# Omnimo_nRF52840.net
KiCad netlist of a schematic drawn in EasyEDA Pro
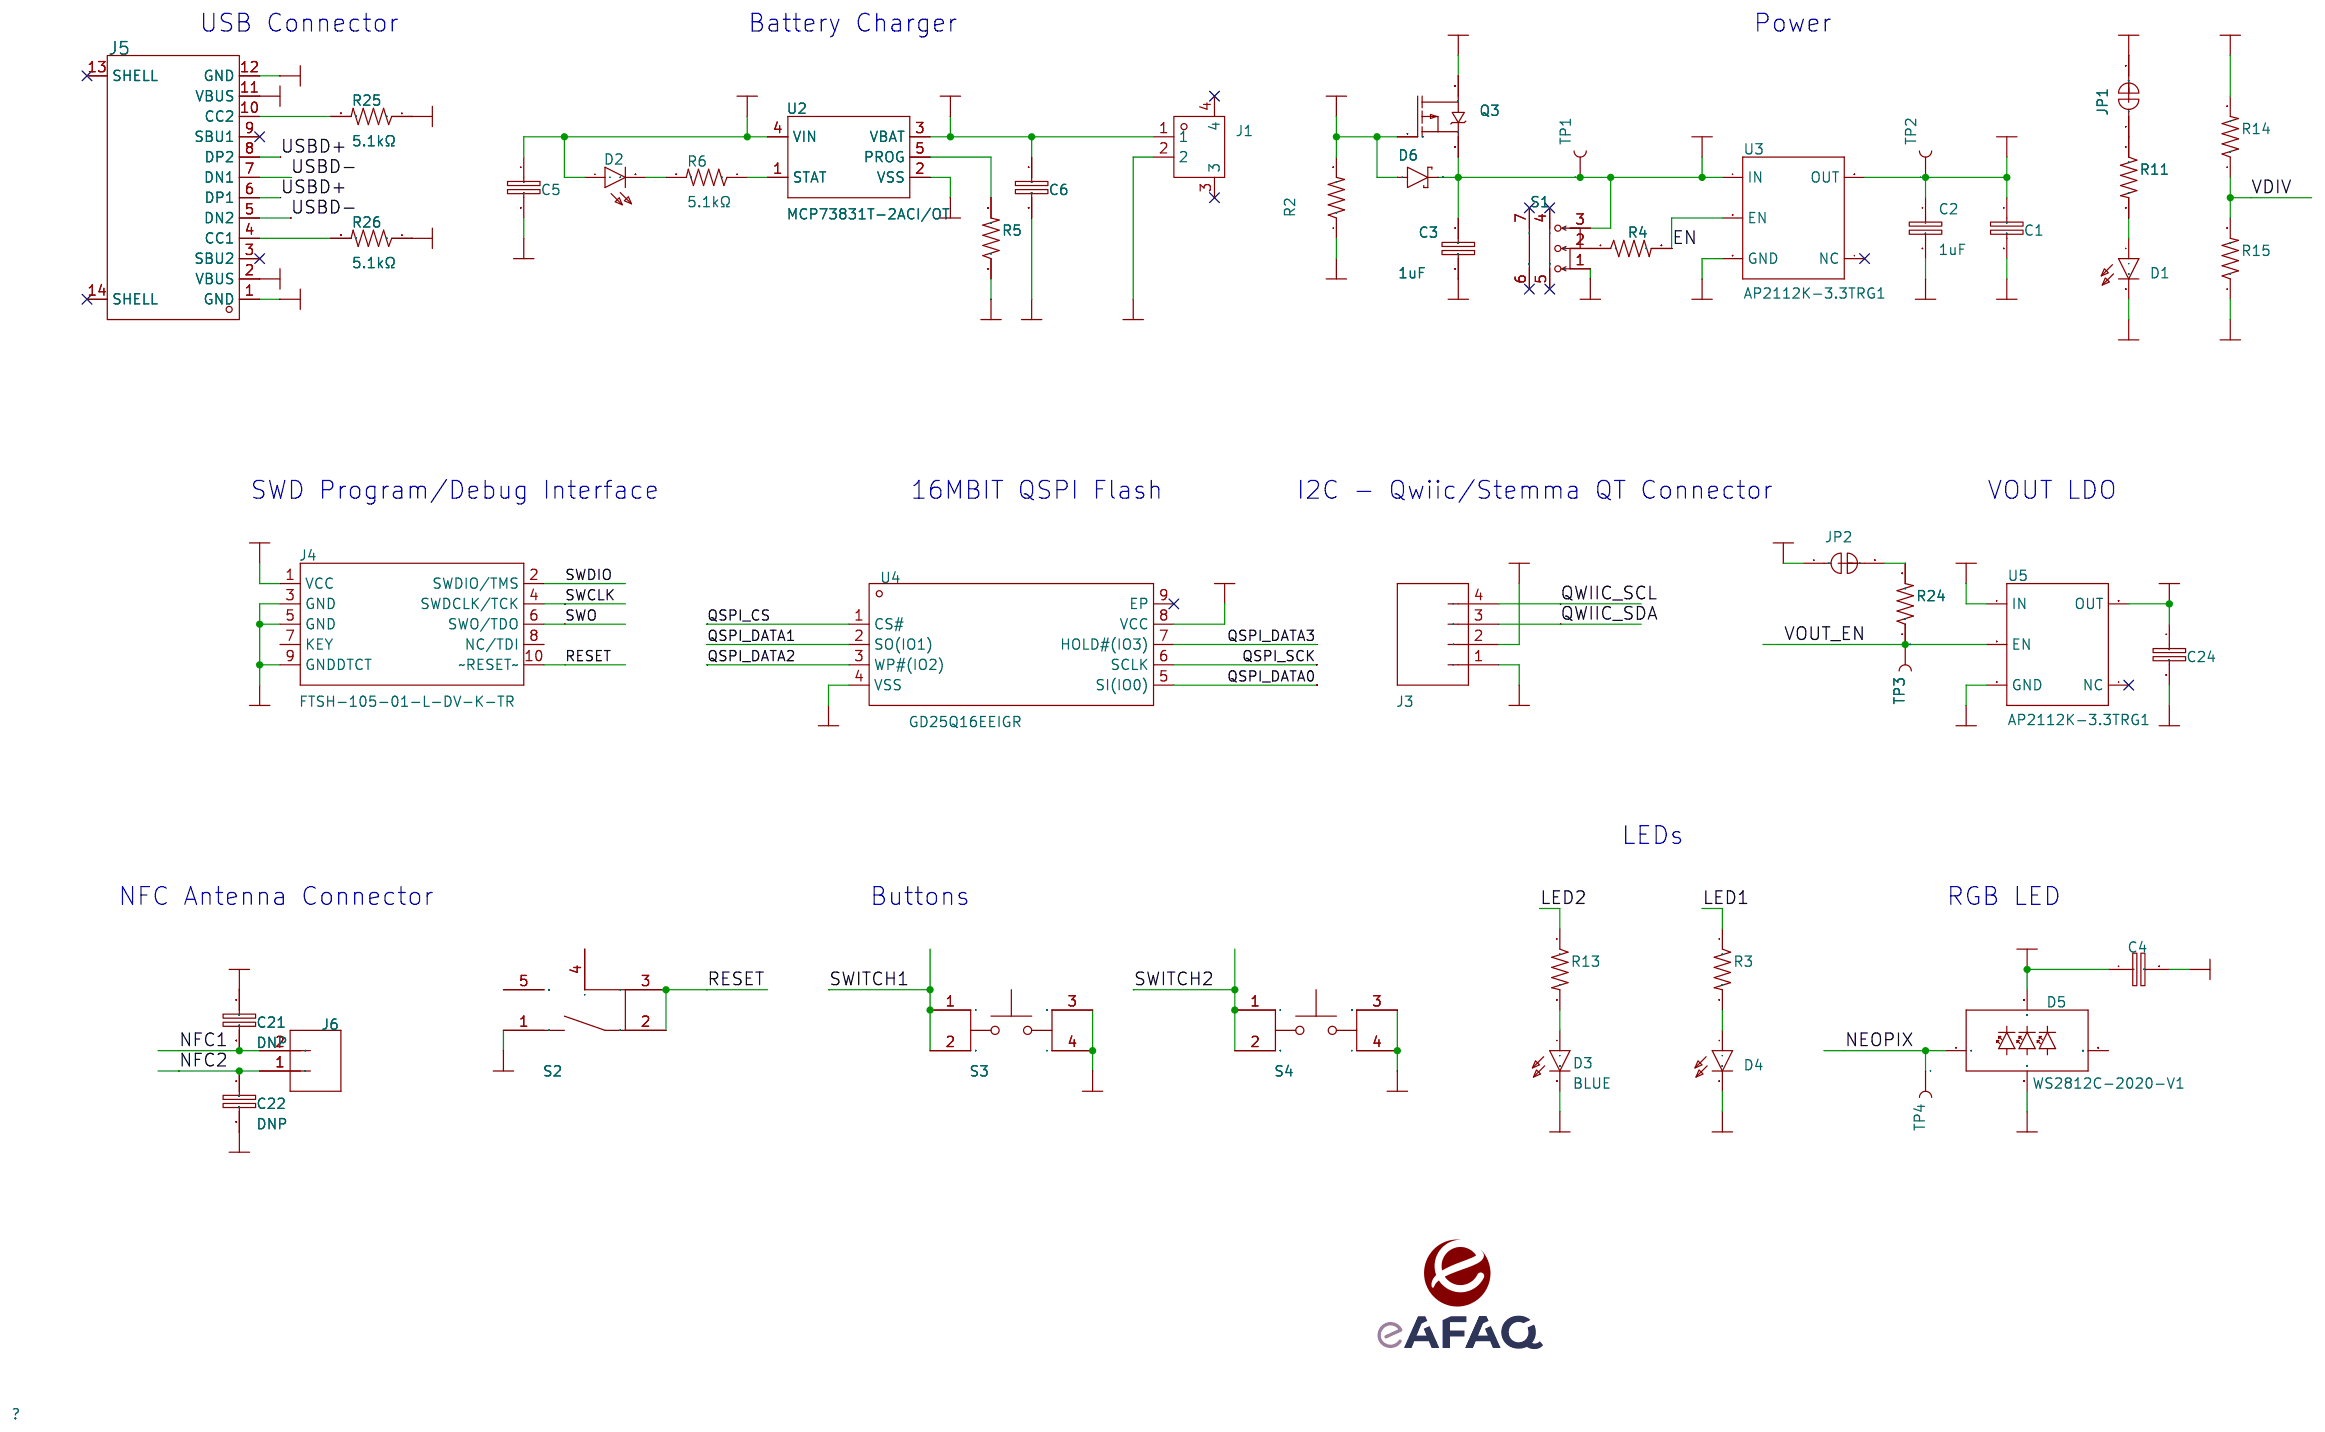
[diagram p0: Omnimo_nrf52840_v1_1_sheet_1]
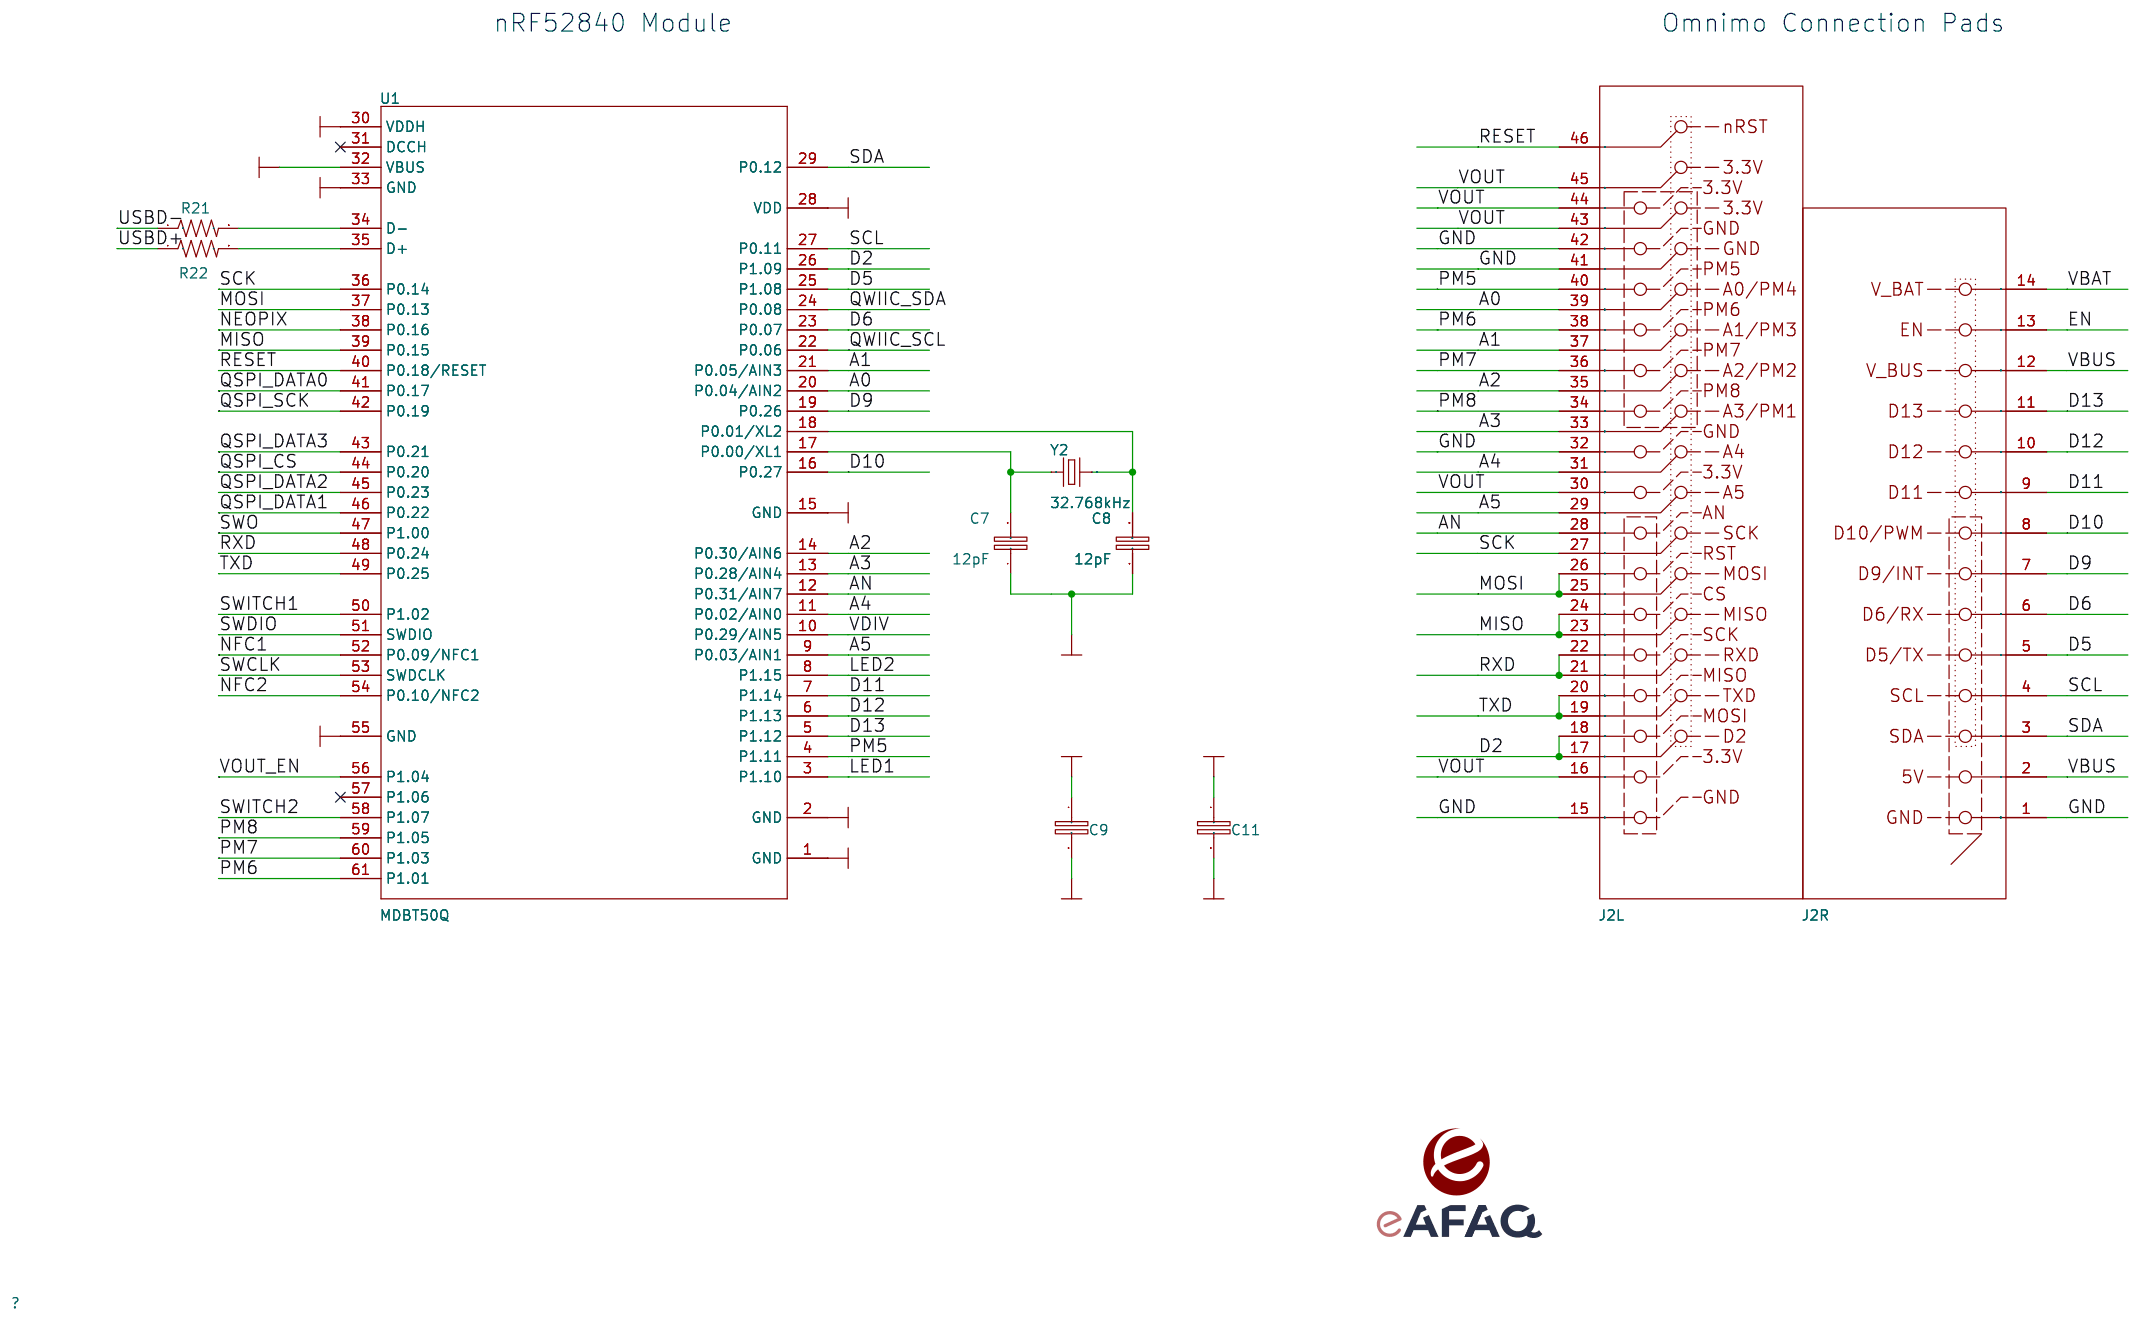
[diagram p1: Omnimo_nrf52840_v1_1_sheet_2]

(export (version "E")
  (design (tool "Eeschema 10.0.6"))
  (components
    (comp (ref "C1")
      (value "10uF")
      (footprint "easyedapro:0603_Nom")
      (fields (field (name "Manufacturer Part") "CC0603KRX5R5BB106"))
      (libsource (lib "easyedapro") (part "10UF-0603-6.3V-20%"))
    )
    (comp (ref "C2")
      (value "1uF")
      (fields
        (field (name "Manufacturer Part") "CL05A105KO5NNNC")
        (field (name "Manufacturer Part Number") "C0402C105K4PAC7867")
      )
      (libsource (lib "easyedapro") (part "1.0UF-0402T-16V-10%"))
    )
    (comp (ref "C3")
      (value "1uF")
      (fields
        (field (name "Manufacturer Part") "CL05A105KO5NNNC")
        (field (name "Manufacturer Part Number") "C0402C105K4PAC7867")
      )
      (libsource (lib "easyedapro") (part "1.0UF-0402T-16V-10%"))
    )
    (comp (ref "C4")
      (value "100nF")
      (fields
        (field (name "Manufacturer Part") "CC0402KRX5R6BB104")
        (field (name "Manufacturer Part Number") "C0402C104K8PACTU")
      )
      (libsource (lib "easyedapro") (part "0.1UF-0603-25V-(+80/-20%)"))
    )
    (comp (ref "C5")
      (value "4.7uF")
      (fields (field (name "Manufacturer Part") "CC0402MRX5R5BB475"))
      (libsource (lib "easyedapro") (part "4.7UF-0603-6.3V-(10%)"))
    )
    (comp (ref "C6")
      (value "4.7uF")
      (fields (field (name "Manufacturer Part") "CC0402MRX5R5BB475"))
      (libsource (lib "easyedapro") (part "4.7UF-0603-6.3V-(10%)"))
    )
    (comp (ref "C21")
      (value "DNP")
      (footprint "easyedapro:0603_Nom")
      (libsource (lib "easyedapro") (part "10UF-0603-6.3V-20%"))
    )
    (comp (ref "C22")
      (value "DNP")
      (footprint "easyedapro:0603_Nom")
      (libsource (lib "easyedapro") (part "10UF-0603-6.3V-20%"))
    )
    (comp (ref "C24")
      (value "10uF")
      (footprint "easyedapro:0603_Nom")
      (fields (field (name "Manufacturer Part") "CC0603KRX5R5BB106"))
      (libsource (lib "easyedapro") (part "10UF-0603-6.3V-20%"))
    )
    (comp (ref "D1")
      (value "RED")
      (fields
        (field (name "Manufacturer Part") "XL-1608SURC-06")
        (field (name "Manufacturer Part Number") "NCD1608W1")
      )
      (libsource (lib "easyedapro") (part "LED-YELLOW0603"))
    )
    (comp (ref "D2")
      (value "ORANGE")
      (fields
        (field (name "Manufacturer Part") "XL-1608UOC-06")
        (field (name "Manufacturer Part Number") "5988050107F")
      )
      (libsource (lib "easyedapro") (part "LED-YELLOW0603"))
    )
    (comp (ref "D3")
      (value "BLUE")
      (footprint "easyedapro:LED-0603_2")
      (fields
        (field (name "Manufacturer") "Dialight")
        (field (name "Manufacturer Part") "XL-1608UBC-04")
        (field (name "Manufacturer Part Number") "5988091107F")
      )
      (libsource (lib "easyedapro") (part "LED-BLUE0603"))
    )
    (comp (ref "D4")
      (value "RED")
      (fields
        (field (name "Manufacturer Part") "XL-1608SURC-06")
        (field (name "Manufacturer Part Number") "NCD1608W1")
      )
      (libsource (lib "easyedapro") (part "LED-YELLOW0603"))
    )
    (comp (ref "D5")
      (value "WS2812C-2020-V1")
      (description "Addressable Lighting Neopixel LED Discrete Red, Green, Blue (RGB) 2.00mm L x 2.00mm W")
      (fields (field (name "Manufacturer Part Number") "WS2812-2020"))
      (libsource (lib "easyedapro") (part "WS2812_2020"))
    )
    (comp (ref "D6")
      (value "BAT60B")
      (fields (field (name "Manufacturer Part Number") "BAT60AE6327HTSA1"))
      (libsource (lib "easyedapro") (part "DIODE-SCHOTTKY-BAT60A"))
    )
    (comp (ref "J1")
      (value "S2B-PH-SM4-TB(LF)(SN)")
      (footprint "easyedapro:CONN-SMD_P2.00_S2B-PH-SM4-TB-LF-SN")
      (fields
        (field (name "Manufacturer") "JST")
        (field (name "Manufacturer Part Number") "S2B-PH-SM4-K-TB (LF)(SN)")
      )
      (libsource (lib "easyedapro") (part "S2B-PH-SM4-TB(LF)(SN)"))
    )
    (comp (ref "J3")
      (value "SM04B-SRSS-TB(LF)(SN)")
      (libsource (lib "easyedapro") (part "JST-4-CONNECTOR-1MM"))
    )
    (comp (ref "J4") (value "FTSH-105-01-L-DV-K-TR") (libsource (lib "easyedapro") (part "CORTEX_DEBUG_PTH")))
    (comp (ref "J5")
      (value "TYPE-C 16PIN 2MD(073)")
      (footprint "easyedapro:USB-C-SMD_TYPE-C-6PIN-2MD-073")
      (fields (field (name "Manufacturer") "SHOU HAN(首韩)"))
      (libsource (lib "easyedapro") (part "TYPE-C 16PIN 2MD(073)"))
    )
    (comp (ref "J6")
      (value "CONN_021X02")
      (footprint "easyedapro:1X02_NFC")
      (libsource (lib "easyedapro") (part "CONN_021X02_NO_SILK"))
    )
    (comp (ref "JP1")
      (value "JUMPER-SMT_2_NC_TRACE_SILK")
      (footprint "easyedapro:SMT-JUMPER_2_NC_TRACE_SILK_2")
      (libsource (lib "easyedapro") (part "JUMPER-SMT_2_NC_TRACE_SILK"))
    )
    (comp (ref "JP2")
      (value "JUMPER-SMT_2_NC_TRACE_SILK")
      (footprint "easyedapro:SMT-JUMPER_2_NC_TRACE_SILK_2")
      (libsource (lib "easyedapro") (part "JUMPER-SMT_2_NC_TRACE_SILK"))
    )
    (comp (ref "Q3") (value "DMG2305UXQ-7") (libsource (lib "easyedapro") (part "MOSFET_PCH-DMG2305UX-7")))
    (comp (ref "R2")
      (value "100kΩ")
      (fields (field (name "Manufacturer Part") "RC0402FR-07100KL"))
      (libsource (lib "easyedapro") (part "10KOHM-0603-1/10W-1%"))
    )
    (comp (ref "R3")
      (value "2.2kΩ")
      (fields
        (field (name "Manufacturer Part") "RC0402FR-072K2L")
        (field (name "Manufacturer Part Number") "RC0402FR-071KL")
      )
      (libsource (lib "easyedapro") (part "1KOHM-0603-1/10W-1%"))
    )
    (comp (ref "R4")
      (value "100kΩ")
      (fields
        (field (name "Manufacturer Part") "RC0402FR-07100KL")
        (field (name "Manufacturer Part Number") "RC0402FR-0710KL")
      )
      (libsource (lib "easyedapro") (part "1KOHM-0603-1/10W-1%"))
    )
    (comp (ref "R5")
      (value "2kΩ")
      (fields (field (name "Manufacturer Part") "RC0402JR-072KL"))
      (libsource (lib "easyedapro") (part "2.0KOHM-0603-1/10W-5%"))
    )
    (comp (ref "R6")
      (value "5.1kΩ")
      (fields (field (name "Manufacturer Part") "RC0402FR-075K1L"))
      (libsource (lib "easyedapro") (part "5.1KOHM-0402T-1/16W-1%"))
    )
    (comp (ref "R11")
      (value "10kΩ")
      (fields
        (field (name "Manufacturer Part") "RC0402FR-0710KL")
        (field (name "Manufacturer Part Number") "RC0402FR-071KL")
      )
      (libsource (lib "easyedapro") (part "1KOHM-0603-1/10W-1%"))
    )
    (comp (ref "R13")
      (value "2.2kΩ")
      (fields
        (field (name "Manufacturer Part") "RC0402FR-072K2L")
        (field (name "Manufacturer Part Number") "RC0402FR-071KL")
      )
      (libsource (lib "easyedapro") (part "1KOHM-0603-1/10W-1%"))
    )
    (comp (ref "R14")
      (value "100kΩ")
      (fields
        (field (name "Manufacturer Part") "RC0402DR-07100KL")
        (field (name "Manufacturer Part Number") "RC0402FR-07100KL")
      )
      (libsource (lib "easyedapro") (part "10KOHM-0603-1/10W-1%"))
    )
    (comp (ref "R15")
      (value "100kΩ")
      (fields
        (field (name "Manufacturer Part") "RC0402DR-07100KL")
        (field (name "Manufacturer Part Number") "RC0402FR-07100KL")
      )
      (libsource (lib "easyedapro") (part "10KOHM-0603-1/10W-1%"))
    )
    (comp (ref "R24")
      (value "100kΩ")
      (fields (field (name "Manufacturer Part") "RC0402FR-07100KL"))
      (libsource (lib "easyedapro") (part "10KOHM-0603-1/10W-1%"))
    )
    (comp (ref "R25")
      (value "5.1kΩ")
      (fields (field (name "Manufacturer Part") "RC0402FR-075K1L"))
      (libsource (lib "easyedapro") (part "5.1KOHM-0402T-1/16W-1%"))
    )
    (comp (ref "R26")
      (value "5.1kΩ")
      (fields (field (name "Manufacturer Part") "RC0402FR-075K1L"))
      (libsource (lib "easyedapro") (part "5.1KOHM-0402T-1/16W-1%"))
    )
    (comp (ref "S1")
      (value "TA-3514-A1-B")
      (footprint "easyedapro:SW-SMD_TA-3514-A1-B")
      (fields (field (name "Manufacturer") "Yuandi(元迪)"))
      (libsource (lib "easyedapro") (part "TA-3514-A1-B"))
    )
    (comp (ref "S2") (value "R-667270") (libsource (lib "easyedapro") (part "Tact Switch - PTS815 Series_1")))
    (comp (ref "S3")
      (value "PTS815SJG250SMTRLFS")
      (libsource (lib "easyedapro") (part "Tact Switch - PTS815 Series"))
    )
    (comp (ref "S4")
      (value "PTS815SJG250SMTRLFS")
      (libsource (lib "easyedapro") (part "Tact Switch - PTS815 Series"))
    )
    (comp (ref "TP1")
      (value "TEST-POINT3X5")
      (footprint "easyedapro:TEST_POINT_1mm")
      (description "Test Point")
      (libsource (lib "easyedapro") (part "TEST-POINT3X5"))
    )
    (comp (ref "TP2")
      (value "TEST-POINT3X5")
      (footprint "easyedapro:TEST_POINT_1mm")
      (description "Test Point")
      (libsource (lib "easyedapro") (part "TEST-POINT3X5"))
    )
    (comp (ref "TP3")
      (value "TEST-POINT3X5")
      (footprint "easyedapro:TEST_POINT_1mm")
      (description "Test Point")
      (libsource (lib "easyedapro") (part "TEST-POINT3X5"))
    )
    (comp (ref "TP4")
      (value "TEST-POINT3X5")
      (footprint "easyedapro:TEST_POINT_1mm")
      (description "Test Point")
      (libsource (lib "easyedapro") (part "TEST-POINT3X5"))
    )
    (comp (ref "U2") (value "MCP73831T-2ACI/OT") (libsource (lib "easyedapro") (part "MCP73831")))
    (comp (ref "U3") (value "AP2112K-3.3TRG1") (libsource (lib "easyedapro") (part "V_REG_AP2112K-3.3V")))
    (comp (ref "U4")
      (value "GD25Q16EEIGR")
      (footprint "easyedapro:USON-8_L3.0-W2.0-P0.50-BL-EP_GD25QXX")
      (fields
        (field (name "Manufacturer") "GigaDevice(兆易创新)")
        (field (name "Manufacturer Part Number") "GD25WQ16EEIGR")
      )
      (libsource (lib "easyedapro") (part "GD25Q16EEIGR"))
    )
    (comp (ref "U5") (value "AP2112K-3.3TRG1") (libsource (lib "easyedapro") (part "V_REG_AP2112K-3.3V")))
    (comp (ref "C7")
      (value "12pF")
      (footprint "easyedapro:0402_NOM")
      (description "12pF, 0402, 50V, 1%")
      (fields (field (name "Manufacturer") "AVX") (field (name "Manufacturer Part") "04025U120FAT2A"))
      (libsource (lib "easyedapro") (part "15PF-0603-50V-5%"))
    )
    (comp (ref "C8")
      (value "12pF")
      (footprint "easyedapro:0402_NOM")
      (description "12pF, 0402, 50V, 1%")
      (fields (field (name "Manufacturer") "AVX") (field (name "Manufacturer Part") "04025U120FAT2A"))
      (libsource (lib "easyedapro") (part "15PF-0603-50V-5%"))
    )
    (comp (ref "C9")
      (value "10uF")
      (footprint "easyedapro:0603_Nom")
      (fields (field (name "Manufacturer Part") "CC0603KRX5R5BB106"))
      (libsource (lib "easyedapro") (part "10UF-0603-6.3V-20%"))
    )
    (comp (ref "C11")
      (value "100nF")
      (fields
        (field (name "Manufacturer Part") "CC0402KRX5R6BB104")
        (field (name "Manufacturer Part Number") "C0402C104K8PACTU")
      )
      (libsource (lib "easyedapro") (part "0.1UF-0603-25V-(+80/-20%)"))
    )
    (comp (ref "J2L")
      (value "omnimo_Header_left")
      (footprint "easyedapro:Omnimo_HDR_Left_nRF52_2 - without silk screen")
      (libsource (lib "easyedapro") (part "omnimo_HDR_Left"))
    )
    (comp (ref "J2R")
      (value "omnimo_Header_right")
      (footprint "easyedapro:Omnimo_HDR_Right_nRF52_2 - without silk screen")
      (libsource (lib "easyedapro") (part "omnimo_HDR_Right"))
    )
    (comp (ref "R21")
      (value "27Ω")
      (footprint "easyedapro:0402_NOM")
      (description "RES 27 OHM 1% 1/10W 0402 SMD")
      (fields
        (field (name "Manufacturer") "Panasonic Electronic Components")
        (field (name "Manufacturer Part") "ERJ-U02F27R0X")
      )
      (libsource (lib "easyedapro") (part "27OHM-0603-1/10W-1%"))
    )
    (comp (ref "R22")
      (value "27Ω")
      (footprint "easyedapro:0402_NOM")
      (description "RES 27 OHM 1% 1/10W 0402 SMD")
      (fields
        (field (name "Manufacturer") "Panasonic Electronic Components")
        (field (name "Manufacturer Part") "ERJ-U02F27R0X")
      )
      (libsource (lib "easyedapro") (part "27OHM-0603-1/10W-1%"))
    )
    (comp (ref "U1")
      (value "MDBT50Q")
      (footprint "easyedapro:MDBT50Q-1MV2")
      (description "MDBT50 Bluetooth Low Energy Module based on Noridc nRF52840")
      (fields (field (name "Manufacturer") "Raytac") (field (name "Manufacturer Part") "MDBT50Q-1MV2"))
      (libsource (lib "easyedapro") (part "MDBT50Q"))
    )
    (comp (ref "Y2")
      (value "32.768kHz")
      (fields (field (name "Manufacturer Part") "ABS07-32.768KHZ-T"))
      (libsource (lib "easyedapro") (part "CRYSTAL-32.768KHZSMD-3.2X1.5"))
    )
  )
  (nets
    (net (code "1") (name "3.3V") (class "Default")
      (node (ref "C1") (pin "1") (pinfunction "1_1") (pintype "unspecified"))
      (node (ref "C11") (pin "1") (pinfunction "1_1") (pintype "unspecified"))
      (node (ref "C2") (pin "1") (pinfunction "1_1") (pintype "unspecified"))
      (node (ref "C4") (pin "1") (pinfunction "1_1") (pintype "unspecified"))
      (node (ref "C9") (pin "1") (pinfunction "1_1") (pintype "unspecified"))
      (node (ref "D5") (pin "VCC") (pinfunction "VCC_VCC") (pintype "unspecified"))
      (node (ref "J4") (pin "1") (pinfunction "VCC_1") (pintype "unspecified"))
      (node (ref "JP1") (pin "2") (pinfunction "2_2") (pintype "unspecified"))
      (node (ref "JP2") (pin "1") (pinfunction "1_1") (pintype "unspecified"))
      (node (ref "TP2") (pin "P$1") (pinfunction "1_P$1") (pintype "unspecified"))
      (node (ref "U1") (pin "28") (pinfunction "VDD_28") (pintype "unspecified"))
      (node (ref "U1") (pin "30") (pinfunction "VDDH_30") (pintype "unspecified"))
      (node (ref "U3") (pin "5") (pinfunction "OUT_5") (pintype "unspecified"))
      (node (ref "U4") (pin "8") (pinfunction "VCC_8") (pintype "unspecified"))
    )
    (net (code "2") (name "A0") (class "Default")
      (node (ref "J2L") (pin "39") (pinfunction "39_39") (pintype "unspecified"))
      (node (ref "U1") (pin "20") (pinfunction "P0.04/AIN2_20") (pintype "unspecified"))
    )
    (net (code "3") (name "A1") (class "Default")
      (node (ref "J2L") (pin "37") (pinfunction "37_37") (pintype "unspecified"))
      (node (ref "U1") (pin "21") (pinfunction "P0.05/AIN3_21") (pintype "unspecified"))
    )
    (net (code "4") (name "A2") (class "Default")
      (node (ref "J2L") (pin "35") (pinfunction "35_35") (pintype "unspecified"))
      (node (ref "U1") (pin "14") (pinfunction "P0.30/AIN6_14") (pintype "unspecified"))
    )
    (net (code "5") (name "A3") (class "Default")
      (node (ref "J2L") (pin "33") (pinfunction "33_33") (pintype "unspecified"))
      (node (ref "U1") (pin "13") (pinfunction "P0.28/AIN4_13") (pintype "unspecified"))
    )
    (net (code "6") (name "A4") (class "Default")
      (node (ref "J2L") (pin "31") (pinfunction "31_31") (pintype "unspecified"))
      (node (ref "U1") (pin "11") (pinfunction "P0.02/AIN0_11") (pintype "unspecified"))
    )
    (net (code "7") (name "A5") (class "Default")
      (node (ref "J2L") (pin "29") (pinfunction "29_29") (pintype "unspecified"))
      (node (ref "U1") (pin "9") (pinfunction "P0.03/AIN1_9") (pintype "unspecified"))
    )
    (net (code "8") (name "AN") (class "Default")
      (node (ref "J2L") (pin "28") (pinfunction "28_28") (pintype "unspecified"))
      (node (ref "U1") (pin "12") (pinfunction "P0.31/AIN7_12") (pintype "unspecified"))
    )
    (net (code "9") (name "D2") (class "Default")
      (node (ref "J2L") (pin "17") (pinfunction "17_17") (pintype "unspecified"))
      (node (ref "J2L") (pin "18") (pinfunction "18_18") (pintype "unspecified"))
      (node (ref "U1") (pin "26") (pinfunction "P1.09_26") (pintype "unspecified"))
    )
    (net (code "10") (name "D5") (class "Default")
      (node (ref "J2R") (pin "5") (pinfunction "5_5") (pintype "unspecified"))
      (node (ref "U1") (pin "25") (pinfunction "P1.08_25") (pintype "unspecified"))
    )
    (net (code "11") (name "D6") (class "Default")
      (node (ref "J2R") (pin "6") (pinfunction "6_6") (pintype "unspecified"))
      (node (ref "U1") (pin "23") (pinfunction "P0.07_23") (pintype "unspecified"))
    )
    (net (code "12") (name "D9") (class "Default")
      (node (ref "J2R") (pin "7") (pinfunction "7_7") (pintype "unspecified"))
      (node (ref "U1") (pin "19") (pinfunction "P0.26_19") (pintype "unspecified"))
    )
    (net (code "13") (name "D10") (class "Default")
      (node (ref "J2R") (pin "8") (pinfunction "8_8") (pintype "unspecified"))
      (node (ref "U1") (pin "16") (pinfunction "P0.27_16") (pintype "unspecified"))
    )
    (net (code "14") (name "D11") (class "Default")
      (node (ref "J2R") (pin "9") (pinfunction "9_9") (pintype "unspecified"))
      (node (ref "U1") (pin "7") (pinfunction "P1.14_7") (pintype "unspecified"))
    )
    (net (code "15") (name "D12") (class "Default")
      (node (ref "J2R") (pin "10") (pinfunction "10_10") (pintype "unspecified"))
      (node (ref "U1") (pin "6") (pinfunction "P1.13_6") (pintype "unspecified"))
    )
    (net (code "16") (name "D13") (class "Default")
      (node (ref "J2R") (pin "11") (pinfunction "11_11") (pintype "unspecified"))
      (node (ref "U1") (pin "5") (pinfunction "P1.12_5") (pintype "unspecified"))
    )
    (net (code "17") (name "EN") (class "Default")
      (node (ref "J2R") (pin "13") (pinfunction "13_13") (pintype "unspecified"))
      (node (ref "R4") (pin "2") (pinfunction "2_2") (pintype "unspecified"))
      (node (ref "U3") (pin "3") (pinfunction "EN_3") (pintype "unspecified"))
    )
    (net (code "18") (name "GND") (class "Default")
      (node (ref "C1") (pin "2") (pinfunction "2_2") (pintype "unspecified"))
      (node (ref "C11") (pin "2") (pinfunction "2_2") (pintype "unspecified"))
      (node (ref "C2") (pin "2") (pinfunction "2_2") (pintype "unspecified"))
      (node (ref "C21") (pin "1") (pinfunction "1_1") (pintype "unspecified"))
      (node (ref "C22") (pin "2") (pinfunction "2_2") (pintype "unspecified"))
      (node (ref "C24") (pin "2") (pinfunction "2_2") (pintype "unspecified"))
      (node (ref "C3") (pin "2") (pinfunction "2_2") (pintype "unspecified"))
      (node (ref "C4") (pin "2") (pinfunction "2_2") (pintype "unspecified"))
      (node (ref "C5") (pin "2") (pinfunction "2_2") (pintype "unspecified"))
      (node (ref "C6") (pin "2") (pinfunction "2_2") (pintype "unspecified"))
      (node (ref "C7") (pin "1") (pinfunction "1_1") (pintype "unspecified"))
      (node (ref "C8") (pin "1") (pinfunction "1_1") (pintype "unspecified"))
      (node (ref "C9") (pin "2") (pinfunction "2_2") (pintype "unspecified"))
      (node (ref "D1") (pin "C") (pinfunction "C_C") (pintype "unspecified"))
      (node (ref "D3") (pin "C") (pinfunction "C_C") (pintype "unspecified"))
      (node (ref "D4") (pin "C") (pinfunction "C_C") (pintype "unspecified"))
      (node (ref "D5") (pin "GND") (pinfunction "GND_GND") (pintype "unspecified"))
      (node (ref "J1") (pin "2") (pinfunction "2_2") (pintype "unspecified"))
      (node (ref "J2L") (pin "15") (pinfunction "15_15") (pintype "unspecified"))
      (node (ref "J2L") (pin "32") (pinfunction "32_32") (pintype "unspecified"))
      (node (ref "J2L") (pin "41") (pinfunction "41_41") (pintype "unspecified"))
      (node (ref "J2L") (pin "42") (pinfunction "42_42") (pintype "unspecified"))
      (node (ref "J2R") (pin "1") (pinfunction "GND_1") (pintype "unspecified"))
      (node (ref "J3") (pin "1") (pinfunction "1_1") (pintype "unspecified"))
      (node (ref "J4") (pin "3") (pinfunction "GND_3") (pintype "unspecified"))
      (node (ref "J4") (pin "5") (pinfunction "GND_5") (pintype "unspecified"))
      (node (ref "J4") (pin "9") (pinfunction "GNDDTCT_9") (pintype "unspecified"))
      (node (ref "J5") (pin "1") (pinfunction "GND_1") (pintype "input"))
      (node (ref "J5") (pin "12") (pinfunction "GND_12") (pintype "input"))
      (node (ref "R15") (pin "1") (pinfunction "1_1") (pintype "unspecified"))
      (node (ref "R2") (pin "1") (pinfunction "1_1") (pintype "unspecified"))
      (node (ref "R25") (pin "1") (pinfunction "1_1") (pintype "unspecified"))
      (node (ref "R26") (pin "1") (pinfunction "1_1") (pintype "unspecified"))
      (node (ref "R5") (pin "1") (pinfunction "1_1") (pintype "unspecified"))
      (node (ref "S1") (pin "1") (pinfunction "1_1") (pintype "unspecified"))
      (node (ref "S2") (pin "1") (pinfunction "1_1") (pintype "unspecified"))
      (node (ref "S3") (pin "3") (pinfunction "3_3") (pintype "unspecified"))
      (node (ref "S3") (pin "4") (pinfunction "4_4") (pintype "unspecified"))
      (node (ref "S4") (pin "3") (pinfunction "3_3") (pintype "unspecified"))
      (node (ref "S4") (pin "4") (pinfunction "4_4") (pintype "unspecified"))
      (node (ref "U1") (pin "1") (pinfunction "GND_1") (pintype "unspecified"))
      (node (ref "U1") (pin "15") (pinfunction "GND_15") (pintype "unspecified"))
      (node (ref "U1") (pin "2") (pinfunction "GND_2") (pintype "unspecified"))
      (node (ref "U1") (pin "33") (pinfunction "GND_33") (pintype "unspecified"))
      (node (ref "U1") (pin "55") (pinfunction "GND_55") (pintype "unspecified"))
      (node (ref "U2") (pin "2") (pinfunction "VSS_2") (pintype "unspecified"))
      (node (ref "U3") (pin "2") (pinfunction "GND_2") (pintype "unspecified"))
      (node (ref "U4") (pin "4") (pinfunction "VSS_4") (pintype "unspecified"))
      (node (ref "U5") (pin "2") (pinfunction "GND_2") (pintype "unspecified"))
    )
    (net (code "19") (name "LED1") (class "Default")
      (node (ref "R3") (pin "1") (pinfunction "1_1") (pintype "unspecified"))
      (node (ref "U1") (pin "3") (pinfunction "P1.10_3") (pintype "unspecified"))
    )
    (net (code "20") (name "LED2") (class "Default")
      (node (ref "R13") (pin "1") (pinfunction "1_1") (pintype "unspecified"))
      (node (ref "U1") (pin "8") (pinfunction "P1.15_8") (pintype "unspecified"))
    )
    (net (code "21") (name "MISO") (class "Default")
      (node (ref "J2L") (pin "23") (pinfunction "23_23") (pintype "unspecified"))
      (node (ref "J2L") (pin "24") (pinfunction "24_24") (pintype "unspecified"))
      (node (ref "U1") (pin "39") (pinfunction "P0.15_39") (pintype "unspecified"))
    )
    (net (code "22") (name "MOSI") (class "Default")
      (node (ref "J2L") (pin "25") (pinfunction "25_25") (pintype "unspecified"))
      (node (ref "J2L") (pin "26") (pinfunction "26_26") (pintype "unspecified"))
      (node (ref "U1") (pin "37") (pinfunction "P0.13_37") (pintype "unspecified"))
    )
    (net (code "23") (name "NEOPIX") (class "Default")
      (node (ref "D5") (pin "DI") (pinfunction "DI_DI") (pintype "unspecified"))
      (node (ref "TP4") (pin "P$1") (pinfunction "1_P$1") (pintype "unspecified"))
      (node (ref "U1") (pin "38") (pinfunction "P0.16_38") (pintype "unspecified"))
    )
    (net (code "24") (name "NFC1") (class "Default")
      (node (ref "C21") (pin "2") (pinfunction "2_2") (pintype "unspecified"))
      (node (ref "J6") (pin "2") (pinfunction "2_2") (pintype "unspecified"))
      (node (ref "U1") (pin "52") (pinfunction "P0.09/NFC1_52") (pintype "unspecified"))
    )
    (net (code "25") (name "NFC2") (class "Default")
      (node (ref "C22") (pin "1") (pinfunction "1_1") (pintype "unspecified"))
      (node (ref "J6") (pin "1") (pinfunction "1_1") (pintype "unspecified"))
      (node (ref "U1") (pin "54") (pinfunction "P0.10/NFC2_54") (pintype "unspecified"))
    )
    (net (code "26") (name "Net-(D1-PadA)") (class "Default")
      (node (ref "D1") (pin "A") (pinfunction "A_A") (pintype "unspecified"))
      (node (ref "R11") (pin "2") (pinfunction "2_2") (pintype "unspecified"))
    )
    (net (code "27") (name "Net-(D2-PadC)") (class "Default")
      (node (ref "D2") (pin "C") (pinfunction "C_C") (pintype "unspecified"))
      (node (ref "R6") (pin "2") (pinfunction "2_2") (pintype "unspecified"))
    )
    (net (code "28") (name "Net-(D3-PadA)") (class "Default")
      (node (ref "D3") (pin "A") (pinfunction "A_A") (pintype "unspecified"))
      (node (ref "R13") (pin "2") (pinfunction "2_2") (pintype "unspecified"))
    )
    (net (code "29") (name "Net-(D4-PadA)") (class "Default")
      (node (ref "D4") (pin "A") (pinfunction "A_A") (pintype "unspecified"))
      (node (ref "R3") (pin "2") (pinfunction "2_2") (pintype "unspecified"))
    )
    (net (code "30") (name "Net-(J5-CC1)") (class "Default")
      (node (ref "J5") (pin "4") (pinfunction "CC1_4") (pintype "input"))
      (node (ref "R26") (pin "2") (pinfunction "2_2") (pintype "unspecified"))
    )
    (net (code "31") (name "Net-(J5-CC2)") (class "Default")
      (node (ref "J5") (pin "10") (pinfunction "CC2_10") (pintype "input"))
      (node (ref "R25") (pin "2") (pinfunction "2_2") (pintype "unspecified"))
    )
    (net (code "32") (name "Net-(JP1-Pad1)") (class "Default")
      (node (ref "JP1") (pin "1") (pinfunction "1_1") (pintype "unspecified"))
      (node (ref "R11") (pin "1") (pinfunction "1_1") (pintype "unspecified"))
    )
    (net (code "33") (name "Net-(JP2-Pad2)") (class "Default")
      (node (ref "JP2") (pin "2") (pinfunction "2_2") (pintype "unspecified"))
      (node (ref "R24") (pin "2") (pinfunction "2_2") (pintype "unspecified"))
    )
    (net (code "34") (name "Net-(R4-Pad1)") (class "Default")
      (node (ref "R4") (pin "1") (pinfunction "1_1") (pintype "unspecified"))
      (node (ref "S1") (pin "2") (pinfunction "2_2") (pintype "unspecified"))
    )
    (net (code "35") (name "Net-(U1-D+)") (class "Default")
      (node (ref "R22") (pin "2") (pinfunction "2_2") (pintype "unspecified"))
      (node (ref "U1") (pin "35") (pinfunction "D+_35") (pintype "unspecified"))
    )
    (net (code "36") (name "Net-(U1-D-)") (class "Default")
      (node (ref "R21") (pin "2") (pinfunction "2_2") (pintype "unspecified"))
      (node (ref "U1") (pin "34") (pinfunction "D-_34") (pintype "unspecified"))
    )
    (net (code "37") (name "Net-(U1-P0.00{slash}XL1)") (class "Default")
      (node (ref "C7") (pin "2") (pinfunction "2_2") (pintype "unspecified"))
      (node (ref "U1") (pin "17") (pinfunction "P0.00/XL1_17") (pintype "unspecified"))
      (node (ref "Y2") (pin "P$1") (pinfunction "1_P$1") (pintype "unspecified"))
    )
    (net (code "38") (name "Net-(U1-P0.01{slash}XL2)") (class "Default")
      (node (ref "C8") (pin "2") (pinfunction "2_2") (pintype "unspecified"))
      (node (ref "U1") (pin "18") (pinfunction "P0.01/XL2_18") (pintype "unspecified"))
      (node (ref "Y2") (pin "P$2") (pinfunction "2_P$2") (pintype "unspecified"))
    )
    (net (code "39") (name "Net-(U2-PROG)") (class "Default")
      (node (ref "R5") (pin "2") (pinfunction "2_2") (pintype "unspecified"))
      (node (ref "U2") (pin "5") (pinfunction "PROG_5") (pintype "unspecified"))
    )
    (net (code "40") (name "Net-(U2-STAT)") (class "Default")
      (node (ref "R6") (pin "1") (pinfunction "1_1") (pintype "unspecified"))
      (node (ref "U2") (pin "1") (pinfunction "STAT_1") (pintype "output"))
    )
    (net (code "41") (name "PM5") (class "Default")
      (node (ref "J2L") (pin "40") (pinfunction "40_40") (pintype "unspecified"))
      (node (ref "U1") (pin "4") (pinfunction "P1.11_4") (pintype "unspecified"))
    )
    (net (code "42") (name "PM6") (class "Default")
      (node (ref "J2L") (pin "38") (pinfunction "38_38") (pintype "unspecified"))
      (node (ref "U1") (pin "61") (pinfunction "P1.01_61") (pintype "unspecified"))
    )
    (net (code "43") (name "PM7") (class "Default")
      (node (ref "J2L") (pin "36") (pinfunction "36_36") (pintype "unspecified"))
      (node (ref "U1") (pin "60") (pinfunction "P1.03_60") (pintype "unspecified"))
    )
    (net (code "44") (name "PM8") (class "Default")
      (node (ref "J2L") (pin "34") (pinfunction "34_34") (pintype "unspecified"))
      (node (ref "U1") (pin "59") (pinfunction "P1.05_59") (pintype "unspecified"))
    )
    (net (code "45") (name "QSPI_CS") (class "Default")
      (node (ref "U1") (pin "44") (pinfunction "P0.20_44") (pintype "unspecified"))
      (node (ref "U4") (pin "1") (pinfunction "CS#_1") (pintype "unspecified"))
    )
    (net (code "46") (name "QSPI_DATA0") (class "Default")
      (node (ref "U1") (pin "41") (pinfunction "P0.17_41") (pintype "unspecified"))
      (node (ref "U4") (pin "5") (pinfunction "SI(IO0)_5") (pintype "unspecified"))
    )
    (net (code "47") (name "QSPI_DATA1") (class "Default")
      (node (ref "U1") (pin "46") (pinfunction "P0.22_46") (pintype "unspecified"))
      (node (ref "U4") (pin "2") (pinfunction "SO(IO1)_2") (pintype "unspecified"))
    )
    (net (code "48") (name "QSPI_DATA2") (class "Default")
      (node (ref "U1") (pin "45") (pinfunction "P0.23_45") (pintype "unspecified"))
      (node (ref "U4") (pin "3") (pinfunction "WP#(IO2)_3") (pintype "unspecified"))
    )
    (net (code "49") (name "QSPI_DATA3") (class "Default")
      (node (ref "U1") (pin "43") (pinfunction "P0.21_43") (pintype "unspecified"))
      (node (ref "U4") (pin "7") (pinfunction "HOLD#(IO3)_7") (pintype "unspecified"))
    )
    (net (code "50") (name "QSPI_SCK") (class "Default")
      (node (ref "U1") (pin "42") (pinfunction "P0.19_42") (pintype "unspecified"))
      (node (ref "U4") (pin "6") (pinfunction "SCLK_6") (pintype "unspecified"))
    )
    (net (code "51") (name "QWIIC_SCL") (class "Default")
      (node (ref "J3") (pin "4") (pinfunction "4_4") (pintype "unspecified"))
      (node (ref "U1") (pin "22") (pinfunction "P0.06_22") (pintype "unspecified"))
    )
    (net (code "52") (name "QWIIC_SDA") (class "Default")
      (node (ref "J3") (pin "3") (pinfunction "3_3") (pintype "unspecified"))
      (node (ref "U1") (pin "24") (pinfunction "P0.08_24") (pintype "unspecified"))
    )
    (net (code "53") (name "RESET") (class "Default")
      (node (ref "J2L") (pin "46") (pinfunction "46_46") (pintype "unspecified"))
      (node (ref "J4") (pin "10") (pinfunction "~RESET~_10") (pintype "unspecified"))
      (node (ref "S2") (pin "2") (pinfunction "2_2") (pintype "unspecified"))
      (node (ref "S2") (pin "3") (pinfunction "3_3") (pintype "unspecified"))
      (node (ref "U1") (pin "40") (pinfunction "P0.18/RESET_40") (pintype "unspecified"))
    )
    (net (code "54") (name "RXD") (class "Default")
      (node (ref "J2L") (pin "21") (pinfunction "21_21") (pintype "unspecified"))
      (node (ref "J2L") (pin "22") (pinfunction "22_22") (pintype "unspecified"))
      (node (ref "U1") (pin "48") (pinfunction "P0.24_48") (pintype "unspecified"))
    )
    (net (code "55") (name "SCK") (class "Default")
      (node (ref "J2L") (pin "27") (pinfunction "27_27") (pintype "unspecified"))
      (node (ref "U1") (pin "36") (pinfunction "P0.14_36") (pintype "unspecified"))
    )
    (net (code "56") (name "SCL") (class "Default")
      (node (ref "J2R") (pin "4") (pinfunction "4_4") (pintype "unspecified"))
      (node (ref "U1") (pin "27") (pinfunction "P0.11_27") (pintype "unspecified"))
    )
    (net (code "57") (name "SDA") (class "Default")
      (node (ref "J2R") (pin "3") (pinfunction "3_3") (pintype "unspecified"))
      (node (ref "U1") (pin "29") (pinfunction "P0.12_29") (pintype "unspecified"))
    )
    (net (code "58") (name "SWCLK") (class "Default")
      (node (ref "J4") (pin "4") (pinfunction "SWDCLK/TCK_4") (pintype "unspecified"))
      (node (ref "U1") (pin "53") (pinfunction "SWDCLK_53") (pintype "unspecified"))
    )
    (net (code "59") (name "SWDIO") (class "Default")
      (node (ref "J4") (pin "2") (pinfunction "SWDIO/TMS_2") (pintype "unspecified"))
      (node (ref "U1") (pin "51") (pinfunction "SWDIO_51") (pintype "unspecified"))
    )
    (net (code "60") (name "SWITCH1") (class "Default")
      (node (ref "S3") (pin "1") (pinfunction "1_1") (pintype "unspecified"))
      (node (ref "S3") (pin "2") (pinfunction "2_2") (pintype "unspecified"))
      (node (ref "U1") (pin "50") (pinfunction "P1.02_50") (pintype "unspecified"))
    )
    (net (code "61") (name "SWITCH2") (class "Default")
      (node (ref "S4") (pin "1") (pinfunction "1_1") (pintype "unspecified"))
      (node (ref "S4") (pin "2") (pinfunction "2_2") (pintype "unspecified"))
      (node (ref "U1") (pin "58") (pinfunction "P1.07_58") (pintype "unspecified"))
    )
    (net (code "62") (name "SWO") (class "Default")
      (node (ref "J4") (pin "6") (pinfunction "SWO/TDO_6") (pintype "unspecified"))
      (node (ref "U1") (pin "47") (pinfunction "P1.00_47") (pintype "unspecified"))
    )
    (net (code "63") (name "TXD") (class "Default")
      (node (ref "J2L") (pin "19") (pinfunction "19_19") (pintype "unspecified"))
      (node (ref "J2L") (pin "20") (pinfunction "20_20") (pintype "unspecified"))
      (node (ref "U1") (pin "49") (pinfunction "P0.25_49") (pintype "unspecified"))
    )
    (net (code "64") (name "USBD+") (class "Default")
      (node (ref "J5") (pin "6") (pinfunction "DP1_6") (pintype "input"))
      (node (ref "J5") (pin "8") (pinfunction "DP2_8") (pintype "input"))
      (node (ref "R22") (pin "1") (pinfunction "1_1") (pintype "unspecified"))
    )
    (net (code "65") (name "USBD-") (class "Default")
      (node (ref "J5") (pin "5") (pinfunction "DN2_5") (pintype "input"))
      (node (ref "J5") (pin "7") (pinfunction "DN1_7") (pintype "input"))
      (node (ref "R21") (pin "1") (pinfunction "1_1") (pintype "unspecified"))
    )
    (net (code "66") (name "VBAT") (class "Default")
      (node (ref "C6") (pin "1") (pinfunction "1_1") (pintype "unspecified"))
      (node (ref "J1") (pin "1") (pinfunction "1_1") (pintype "unspecified"))
      (node (ref "J2R") (pin "14") (pinfunction "14_14") (pintype "unspecified"))
      (node (ref "Q3") (pin "3") (pinfunction "D_3") (pintype "unspecified"))
      (node (ref "R14") (pin "2") (pinfunction "2_2") (pintype "unspecified"))
      (node (ref "U2") (pin "3") (pinfunction "VBAT_3") (pintype "unspecified"))
    )
    (net (code "67") (name "VBUS") (class "Default")
      (node (ref "C5") (pin "1") (pinfunction "1_1") (pintype "unspecified"))
      (node (ref "D2") (pin "A") (pinfunction "A_A") (pintype "unspecified"))
      (node (ref "D6") (pin "A") (pinfunction "A_A") (pintype "unspecified"))
      (node (ref "J2R") (pin "12") (pinfunction "12_12") (pintype "unspecified"))
      (node (ref "J2R") (pin "2") (pinfunction "5V_2") (pintype "unspecified"))
      (node (ref "J5") (pin "11") (pinfunction "VBUS_11") (pintype "input"))
      (node (ref "J5") (pin "2") (pinfunction "VBUS_2") (pintype "input"))
      (node (ref "Q3") (pin "1") (pinfunction "G_1") (pintype "unspecified"))
      (node (ref "R2") (pin "2") (pinfunction "2_2") (pintype "unspecified"))
      (node (ref "U1") (pin "32") (pinfunction "VBUS_32") (pintype "unspecified"))
      (node (ref "U2") (pin "4") (pinfunction "VIN_4") (pintype "unspecified"))
    )
    (net (code "68") (name "VDIV") (class "Default")
      (node (ref "R14") (pin "1") (pinfunction "1_1") (pintype "unspecified"))
      (node (ref "R15") (pin "2") (pinfunction "2_2") (pintype "unspecified"))
      (node (ref "U1") (pin "10") (pinfunction "P0.29/AIN5_10") (pintype "unspecified"))
    )
    (net (code "69") (name "VIN") (class "Default")
      (node (ref "C3") (pin "1") (pinfunction "1_1") (pintype "unspecified"))
      (node (ref "D6") (pin "C") (pinfunction "C_C") (pintype "unspecified"))
      (node (ref "Q3") (pin "2") (pinfunction "S_2") (pintype "unspecified"))
      (node (ref "S1") (pin "3") (pinfunction "3_3") (pintype "unspecified"))
      (node (ref "TP1") (pin "P$1") (pinfunction "1_P$1") (pintype "unspecified"))
      (node (ref "U3") (pin "1") (pinfunction "IN_1") (pintype "unspecified"))
      (node (ref "U5") (pin "1") (pinfunction "IN_1") (pintype "unspecified"))
    )
    (net (code "70") (name "VOUT") (class "Default")
      (node (ref "C24") (pin "1") (pinfunction "1_1") (pintype "unspecified"))
      (node (ref "J2L") (pin "16") (pinfunction "16_16") (pintype "unspecified"))
      (node (ref "J2L") (pin "30") (pinfunction "30_30") (pintype "unspecified"))
      (node (ref "J2L") (pin "43") (pinfunction "43_43") (pintype "unspecified"))
      (node (ref "J2L") (pin "44") (pinfunction "44_44") (pintype "unspecified"))
      (node (ref "J2L") (pin "45") (pinfunction "45_45") (pintype "unspecified"))
      (node (ref "J3") (pin "2") (pinfunction "2_2") (pintype "unspecified"))
      (node (ref "U5") (pin "5") (pinfunction "OUT_5") (pintype "unspecified"))
    )
    (net (code "71") (name "VOUT_EN") (class "Default")
      (node (ref "R24") (pin "1") (pinfunction "1_1") (pintype "unspecified"))
      (node (ref "TP3") (pin "P$1") (pinfunction "1_P$1") (pintype "unspecified"))
      (node (ref "U1") (pin "56") (pinfunction "P1.04_56") (pintype "unspecified"))
      (node (ref "U5") (pin "3") (pinfunction "EN_3") (pintype "unspecified"))
    )
    (net (code "72") (name "unconnected-(D5-PadDO)") (class "Default")
      (node (ref "D5") (pin "DO") (pinfunction "DO_DO") (pintype "unspecified"))
    )
    (net (code "73") (name "unconnected-(J1-Pad3)") (class "Default")
      (node (ref "J1") (pin "3") (pinfunction "3_3") (pintype "unspecified+no_connect"))
    )
    (net (code "74") (name "unconnected-(J1-Pad4)") (class "Default")
      (node (ref "J1") (pin "4") (pinfunction "4_4") (pintype "unspecified+no_connect"))
    )
    (net (code "75") (name "unconnected-(J4-KEY-Pad7)") (class "Default")
      (node (ref "J4") (pin "7") (pinfunction "KEY_7") (pintype "unspecified"))
    )
    (net (code "76") (name "unconnected-(J4-NC{slash}TDI-Pad8)") (class "Default")
      (node (ref "J4") (pin "8") (pinfunction "NC/TDI_8") (pintype "unspecified"))
    )
    (net (code "77") (name "unconnected-(J5-SBU1-Pad9)") (class "Default")
      (node (ref "J5") (pin "9") (pinfunction "SBU1_9") (pintype "input+no_connect"))
    )
    (net (code "78") (name "unconnected-(J5-SBU2-Pad3)") (class "Default")
      (node (ref "J5") (pin "3") (pinfunction "SBU2_3") (pintype "input+no_connect"))
    )
    (net (code "79") (name "unconnected-(J5-SHELL-Pad13)") (class "Default")
      (node (ref "J5") (pin "13") (pinfunction "SHELL_13") (pintype "input+no_connect"))
    )
    (net (code "80") (name "unconnected-(J5-SHELL-Pad14)") (class "Default")
      (node (ref "J5") (pin "14") (pinfunction "SHELL_14") (pintype "input+no_connect"))
    )
    (net (code "81") (name "unconnected-(S1-Pad4)") (class "Default")
      (node (ref "S1") (pin "4") (pinfunction "4_4") (pintype "unspecified+no_connect"))
    )
    (net (code "82") (name "unconnected-(S1-Pad5)") (class "Default")
      (node (ref "S1") (pin "5") (pinfunction "5_5") (pintype "unspecified+no_connect"))
    )
    (net (code "83") (name "unconnected-(S1-Pad6)") (class "Default")
      (node (ref "S1") (pin "6") (pinfunction "6_6") (pintype "unspecified+no_connect"))
    )
    (net (code "84") (name "unconnected-(S1-Pad7)") (class "Default")
      (node (ref "S1") (pin "7") (pinfunction "7_7") (pintype "unspecified+no_connect"))
    )
    (net (code "85") (name "unconnected-(S2-Pad4)") (class "Default")
      (node (ref "S2") (pin "4") (pinfunction "4_4") (pintype "unspecified"))
    )
    (net (code "86") (name "unconnected-(S2-Pad5)") (class "Default")
      (node (ref "S2") (pin "5") (pinfunction "5_5") (pintype "unspecified"))
    )
    (net (code "87") (name "unconnected-(U1-DCCH-Pad31)") (class "Default")
      (node (ref "U1") (pin "31") (pinfunction "DCCH_31") (pintype "unspecified+no_connect"))
    )
    (net (code "88") (name "unconnected-(U1-P1.06-Pad57)") (class "Default")
      (node (ref "U1") (pin "57") (pinfunction "P1.06_57") (pintype "unspecified+no_connect"))
    )
    (net (code "89") (name "unconnected-(U3-NC-Pad4)") (class "Default")
      (node (ref "U3") (pin "4") (pinfunction "NC_4") (pintype "unspecified+no_connect"))
    )
    (net (code "90") (name "unconnected-(U4-EP-Pad9)") (class "Default")
      (node (ref "U4") (pin "9") (pinfunction "EP_9") (pintype "unspecified+no_connect"))
    )
    (net (code "91") (name "unconnected-(U5-NC-Pad4)") (class "Default")
      (node (ref "U5") (pin "4") (pinfunction "NC_4") (pintype "unspecified+no_connect"))
    )
  )
)
